# PS-VCO.net
KiCad netlist of a schematic drawn in EAGLE
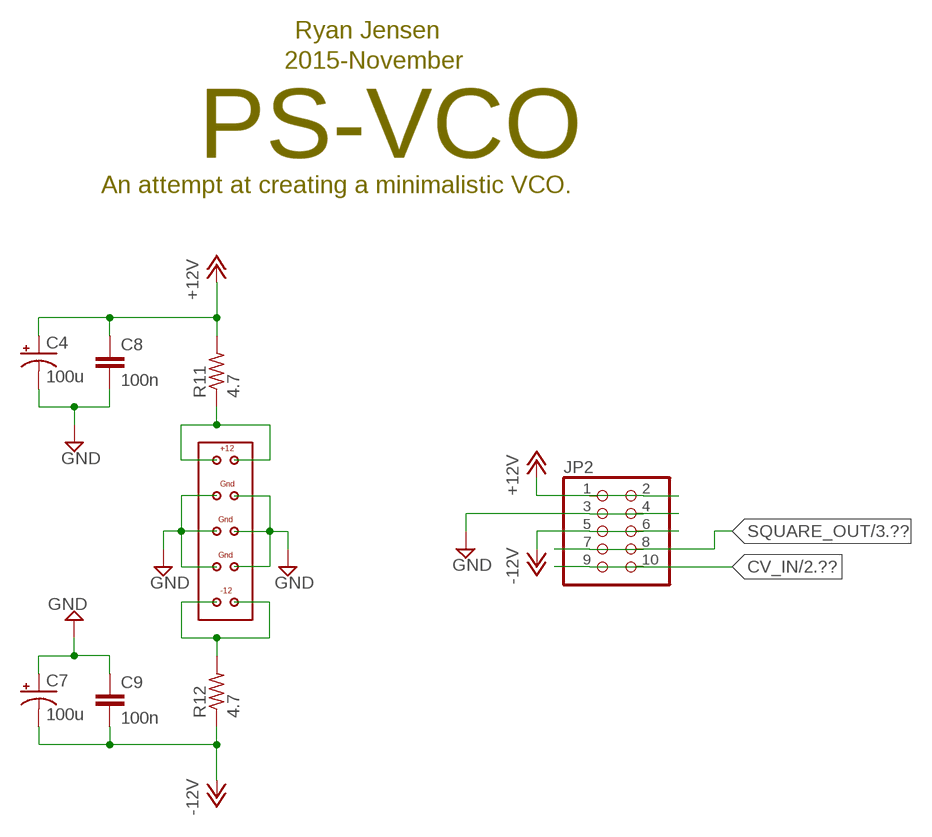
[diagram p0: schematic, sheet 1]
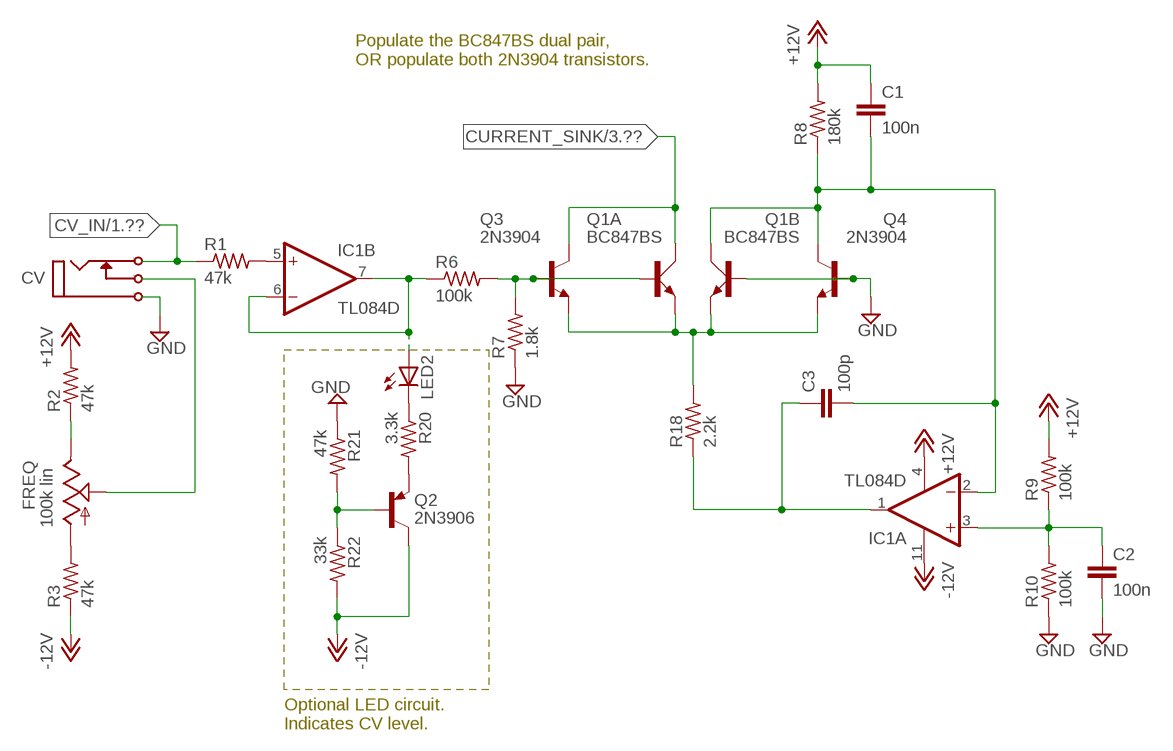
[diagram p1: schematic, sheet 2]
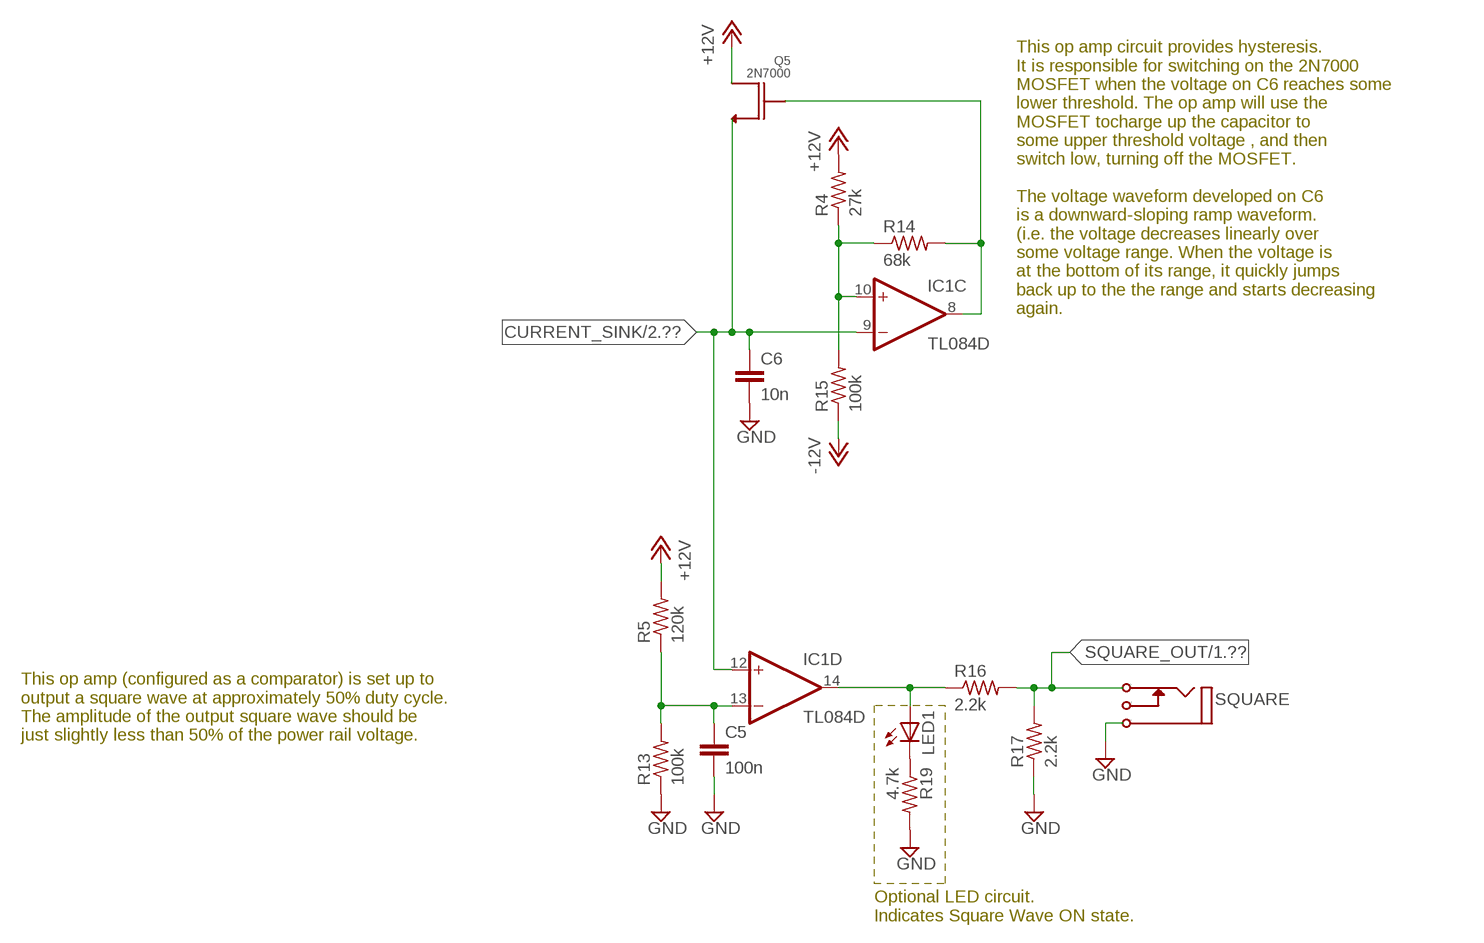
[diagram p2: schematic, sheet 3]

(export (version "E")
  (design (tool "Eeschema 10.0.6"))
  (components
    (comp (ref "C4")
      (value "100u")
      (footprint "eagle-import:E2,5-7")
      (libsource (lib "eagle-import") (part "CPOL-USE2.5-7"))
    )
    (comp (ref "C7")
      (value "100u")
      (footprint "eagle-import:E2,5-7")
      (libsource (lib "eagle-import") (part "CPOL-USE2.5-7"))
    )
    (comp (ref "C8")
      (value "100n")
      (footprint "eagle-import:C0603")
      (libsource (lib "eagle-import") (part "C-EUC0603"))
    )
    (comp (ref "C9")
      (value "100n")
      (footprint "eagle-import:C0603")
      (libsource (lib "eagle-import") (part "C-EUC0603"))
    )
    (comp (ref "JP2")
      (value "PINHD-2X5")
      (footprint "eagle-import:2X05")
      (libsource (lib "eagle-import") (part "PINHD-2X5"))
    )
    (comp (ref "R11")
      (value "4.7")
      (footprint "eagle-import:R0603")
      (libsource (lib "eagle-import") (part "R-US_R0603"))
    )
    (comp (ref "R12")
      (value "4.7")
      (footprint "eagle-import:R0603")
      (libsource (lib "eagle-import") (part "R-US_R0603"))
    )
    (comp (ref "U$3")
      (value "EURORACK-POWER")
      (footprint "eagle-import:EURORACK-POWER")
      (libsource (lib "eagle-import") (part "EURORACK-POWER"))
    )
    (comp (ref "C5")
      (value "100n")
      (footprint "eagle-import:C0603")
      (libsource (lib "eagle-import") (part "C-EUC0603"))
    )
    (comp (ref "C6")
      (value "10n")
      (footprint "eagle-import:C0603")
      (libsource (lib "eagle-import") (part "C-EUC0603"))
    )
    (comp (ref "IC1")
      (value "TL084D")
      (footprint "eagle-import:SO14")
      (libsource (lib "eagle-import") (part "TL084D"))
    )
    (comp (ref "LED1")
      (value "LED_ELD260")
      (footprint "eagle-import:LED_LD260")
      (libsource (lib "eagle-import") (part "LED_ELD260"))
    )
    (comp (ref "Q5")
      (value "2N7000")
      (footprint "eagle-import:2N7000")
      (libsource (lib "eagle-import") (part "2N7000"))
    )
    (comp (ref "R4")
      (value "27k")
      (footprint "eagle-import:R0603")
      (libsource (lib "eagle-import") (part "R-US_R0603"))
    )
    (comp (ref "R5")
      (value "120k")
      (footprint "eagle-import:R0603")
      (libsource (lib "eagle-import") (part "R-US_R0603"))
    )
    (comp (ref "R13")
      (value "100k")
      (footprint "eagle-import:R0603")
      (libsource (lib "eagle-import") (part "R-US_R0603"))
    )
    (comp (ref "R14")
      (value "68k")
      (footprint "eagle-import:R0603")
      (libsource (lib "eagle-import") (part "R-US_R0603"))
    )
    (comp (ref "R15")
      (value "100k")
      (footprint "eagle-import:R0603")
      (libsource (lib "eagle-import") (part "R-US_R0603"))
    )
    (comp (ref "R16")
      (value "2.2k")
      (footprint "eagle-import:R0603")
      (libsource (lib "eagle-import") (part "R-US_R0603"))
    )
    (comp (ref "R17")
      (value "2.2k")
      (footprint "eagle-import:R0603")
      (libsource (lib "eagle-import") (part "R-US_R0603"))
    )
    (comp (ref "R19")
      (value "4.7k")
      (footprint "eagle-import:R0603")
      (libsource (lib "eagle-import") (part "R-US_R0603"))
    )
    (comp (ref "SQUARE")
      (value "I/O")
      (footprint "eagle-import:MONO_JACK")
      (libsource (lib "eagle-import") (part "MONO_JACK"))
    )
    (comp (ref "C1")
      (value "100n")
      (footprint "eagle-import:C0603")
      (libsource (lib "eagle-import") (part "C-EUC0603"))
    )
    (comp (ref "C2")
      (value "100n")
      (footprint "eagle-import:C0603")
      (libsource (lib "eagle-import") (part "C-EUC0603"))
    )
    (comp (ref "C3")
      (value "100p")
      (footprint "eagle-import:C0603")
      (libsource (lib "eagle-import") (part "C-EUC0603"))
    )
    (comp (ref "CV")
      (value "CV")
      (footprint "eagle-import:MONO_JACK")
      (libsource (lib "eagle-import") (part "MONO_JACK"))
    )
    (comp (ref "FREQ")
      (value "100k lin")
      (footprint "eagle-import:B64Y")
      (libsource (lib "eagle-import") (part "TRIM_US-B64Y"))
    )
    (comp (ref "LED2")
      (value "LED_ELD260")
      (footprint "eagle-import:LED_LD260")
      (libsource (lib "eagle-import") (part "LED_ELD260"))
    )
    (comp (ref "Q1")
      (value "BC847BS")
      (footprint "eagle-import:SOT363_PHILIPS")
      (libsource (lib "eagle-import") (part "BC847BS"))
    )
    (comp (ref "Q2")
      (value "2N3906")
      (footprint "eagle-import:TO92")
      (libsource (lib "eagle-import") (part "2N3906"))
    )
    (comp (ref "Q3")
      (value "2N3904")
      (footprint "eagle-import:TO92")
      (libsource (lib "eagle-import") (part "2N3904"))
    )
    (comp (ref "Q4")
      (value "2N3904")
      (footprint "eagle-import:TO92")
      (libsource (lib "eagle-import") (part "2N3904"))
    )
    (comp (ref "R1")
      (value "47k")
      (footprint "eagle-import:R0603")
      (libsource (lib "eagle-import") (part "R-US_R0603"))
    )
    (comp (ref "R2")
      (value "47k")
      (footprint "eagle-import:R0603")
      (libsource (lib "eagle-import") (part "R-US_R0603"))
    )
    (comp (ref "R3")
      (value "47k")
      (footprint "eagle-import:R0603")
      (libsource (lib "eagle-import") (part "R-US_R0603"))
    )
    (comp (ref "R6")
      (value "100k")
      (footprint "eagle-import:R0603")
      (libsource (lib "eagle-import") (part "R-US_R0603"))
    )
    (comp (ref "R7")
      (value "1.8k")
      (footprint "eagle-import:R0603")
      (libsource (lib "eagle-import") (part "R-US_R0603"))
    )
    (comp (ref "R8")
      (value "180k")
      (footprint "eagle-import:R0603")
      (libsource (lib "eagle-import") (part "R-US_R0603"))
    )
    (comp (ref "R9")
      (value "100k")
      (footprint "eagle-import:R0603")
      (libsource (lib "eagle-import") (part "R-US_R0603"))
    )
    (comp (ref "R10")
      (value "100k")
      (footprint "eagle-import:R0603")
      (libsource (lib "eagle-import") (part "R-US_R0603"))
    )
    (comp (ref "R18")
      (value "2.2k")
      (footprint "eagle-import:R0603")
      (libsource (lib "eagle-import") (part "R-US_R0603"))
    )
    (comp (ref "R20")
      (value "3.3k")
      (footprint "eagle-import:R0603")
      (libsource (lib "eagle-import") (part "R-US_R0603"))
    )
    (comp (ref "R21")
      (value "47k")
      (footprint "eagle-import:R0603")
      (libsource (lib "eagle-import") (part "R-US_R0603"))
    )
    (comp (ref "R22")
      (value "33k")
      (footprint "eagle-import:R0603")
      (libsource (lib "eagle-import") (part "R-US_R0603"))
    )
  )
  (nets
    (net (code "1") (name "+12V") (class "Default")
      (node (ref "C1") (pin "1") (pinfunction "1_1") (pintype "passive"))
      (node (ref "C4") (pin "+") (pinfunction "+_+") (pintype "passive"))
      (node (ref "C8") (pin "1") (pinfunction "1_1") (pintype "passive"))
      (node (ref "IC1") (pin "4") (pinfunction "V+_4") (pintype "power_in"))
      (node (ref "JP2") (pin "1") (pinfunction "1_1") (pintype "passive"))
      (node (ref "JP2") (pin "2") (pinfunction "2_2") (pintype "passive"))
      (node (ref "Q5") (pin "D") (pinfunction "D_D") (pintype "bidirectional"))
      (node (ref "R11") (pin "2") (pinfunction "2_2") (pintype "passive"))
      (node (ref "R2") (pin "2") (pinfunction "2_2") (pintype "passive"))
      (node (ref "R4") (pin "2") (pinfunction "2_2") (pintype "passive"))
      (node (ref "R5") (pin "2") (pinfunction "2_2") (pintype "passive"))
      (node (ref "R8") (pin "2") (pinfunction "2_2") (pintype "passive"))
      (node (ref "R9") (pin "2") (pinfunction "2_2") (pintype "passive"))
    )
    (net (code "2") (name "-12V") (class "Default")
      (node (ref "C7") (pin "-") (pinfunction "-_-") (pintype "passive"))
      (node (ref "C9") (pin "2") (pinfunction "2_2") (pintype "passive"))
      (node (ref "IC1") (pin "11") (pinfunction "V-_11") (pintype "power_in"))
      (node (ref "JP2") (pin "5") (pinfunction "5_5") (pintype "passive"))
      (node (ref "JP2") (pin "6") (pinfunction "6_6") (pintype "passive"))
      (node (ref "Q2") (pin "1") (pinfunction "C_1") (pintype "passive"))
      (node (ref "R12") (pin "1") (pinfunction "1_1") (pintype "passive"))
      (node (ref "R15") (pin "1") (pinfunction "1_1") (pintype "passive"))
      (node (ref "R22") (pin "2") (pinfunction "2_2") (pintype "passive"))
      (node (ref "R3") (pin "1") (pinfunction "1_1") (pintype "passive"))
    )
    (net (code "3") (name "CURRENT_SINK") (class "Default")
      (node (ref "C6") (pin "1") (pinfunction "1_1") (pintype "passive"))
      (node (ref "IC1") (pin "12") (pinfunction "+IN_12") (pintype "input"))
      (node (ref "IC1") (pin "9") (pinfunction "-IN_9") (pintype "input"))
      (node (ref "Q1") (pin "6") (pinfunction "C_6") (pintype "passive"))
      (node (ref "Q3") (pin "1") (pinfunction "C_1") (pintype "passive"))
      (node (ref "Q5") (pin "S") (pinfunction "S_S") (pintype "bidirectional"))
    )
    (net (code "4") (name "CV_IN") (class "Default")
      (node (ref "CV") (pin "P$2") (pinfunction "P2_P$2") (pintype "bidirectional"))
      (node (ref "JP2") (pin "10") (pinfunction "10_10") (pintype "passive"))
      (node (ref "JP2") (pin "9") (pinfunction "9_9") (pintype "passive"))
      (node (ref "R1") (pin "1") (pinfunction "1_1") (pintype "passive"))
    )
    (net (code "5") (name "GND") (class "Default")
      (node (ref "C2") (pin "2") (pinfunction "2_2") (pintype "passive"))
      (node (ref "C4") (pin "-") (pinfunction "-_-") (pintype "passive"))
      (node (ref "C5") (pin "2") (pinfunction "2_2") (pintype "passive"))
      (node (ref "C6") (pin "2") (pinfunction "2_2") (pintype "passive"))
      (node (ref "C7") (pin "+") (pinfunction "+_+") (pintype "passive"))
      (node (ref "C8") (pin "2") (pinfunction "2_2") (pintype "passive"))
      (node (ref "C9") (pin "1") (pinfunction "1_1") (pintype "passive"))
      (node (ref "CV") (pin "P$1") (pinfunction "P$1_P$1") (pintype "bidirectional"))
      (node (ref "JP2") (pin "3") (pinfunction "3_3") (pintype "passive"))
      (node (ref "JP2") (pin "4") (pinfunction "4_4") (pintype "passive"))
      (node (ref "Q1") (pin "5") (pinfunction "B_5") (pintype "passive"))
      (node (ref "Q4") (pin "2") (pinfunction "B_2") (pintype "passive"))
      (node (ref "R10") (pin "1") (pinfunction "1_1") (pintype "passive"))
      (node (ref "R13") (pin "1") (pinfunction "1_1") (pintype "passive"))
      (node (ref "R17") (pin "1") (pinfunction "1_1") (pintype "passive"))
      (node (ref "R19") (pin "2") (pinfunction "2_2") (pintype "passive"))
      (node (ref "R21") (pin "1") (pinfunction "1_1") (pintype "passive"))
      (node (ref "R7") (pin "1") (pinfunction "1_1") (pintype "passive"))
      (node (ref "SQUARE") (pin "P$1") (pinfunction "P$1_P$1") (pintype "bidirectional"))
      (node (ref "U$3") (pin "P$3") (pinfunction "P$3_P$3") (pintype "bidirectional"))
      (node (ref "U$3") (pin "P$4") (pinfunction "P$4_P$4") (pintype "bidirectional"))
      (node (ref "U$3") (pin "P$5") (pinfunction "P$5_P$5") (pintype "bidirectional"))
      (node (ref "U$3") (pin "P$6") (pinfunction "P$6_P$6") (pintype "bidirectional"))
      (node (ref "U$3") (pin "P$7") (pinfunction "P$7_P$7") (pintype "bidirectional"))
      (node (ref "U$3") (pin "P$8") (pinfunction "P$8_P$8") (pintype "bidirectional"))
    )
    (net (code "6") (name "Net-(CV-P3)") (class "Default")
      (node (ref "CV") (pin "P$3") (pinfunction "P3_P$3") (pintype "bidirectional"))
      (node (ref "FREQ") (pin "S") (pinfunction "S_S") (pintype "passive"))
    )
    (net (code "7") (name "Net-(FREQ-PadA)") (class "Default")
      (node (ref "FREQ") (pin "A") (pinfunction "A_A") (pintype "passive"))
      (node (ref "R3") (pin "2") (pinfunction "2_2") (pintype "passive"))
    )
    (net (code "8") (name "Net-(FREQ-PadE)") (class "Default")
      (node (ref "FREQ") (pin "E") (pinfunction "E_E") (pintype "passive"))
      (node (ref "R2") (pin "1") (pinfunction "1_1") (pintype "passive"))
    )
    (net (code "9") (name "Net-(IC1A-+IN)") (class "Default")
      (node (ref "C2") (pin "1") (pinfunction "1_1") (pintype "passive"))
      (node (ref "IC1") (pin "3") (pinfunction "+IN_3") (pintype "input"))
      (node (ref "R10") (pin "2") (pinfunction "2_2") (pintype "passive"))
      (node (ref "R9") (pin "1") (pinfunction "1_1") (pintype "passive"))
    )
    (net (code "10") (name "Net-(IC1A--IN)") (class "Default")
      (node (ref "C1") (pin "2") (pinfunction "2_2") (pintype "passive"))
      (node (ref "C3") (pin "2") (pinfunction "2_2") (pintype "passive"))
      (node (ref "IC1") (pin "2") (pinfunction "-IN_2") (pintype "input"))
      (node (ref "Q1") (pin "3") (pinfunction "C_3") (pintype "passive"))
      (node (ref "Q4") (pin "1") (pinfunction "C_1") (pintype "passive"))
      (node (ref "R8") (pin "1") (pinfunction "1_1") (pintype "passive"))
    )
    (net (code "11") (name "Net-(IC1A-OUT)") (class "Default")
      (node (ref "C3") (pin "1") (pinfunction "1_1") (pintype "passive"))
      (node (ref "IC1") (pin "1") (pinfunction "OUT_1") (pintype "output"))
      (node (ref "R18") (pin "1") (pinfunction "1_1") (pintype "passive"))
    )
    (net (code "12") (name "Net-(IC1B-+IN)") (class "Default")
      (node (ref "IC1") (pin "5") (pinfunction "+IN_5") (pintype "input"))
      (node (ref "R1") (pin "2") (pinfunction "2_2") (pintype "passive"))
    )
    (net (code "13") (name "Net-(IC1B--IN)") (class "Default")
      (node (ref "IC1") (pin "6") (pinfunction "-IN_6") (pintype "input"))
      (node (ref "IC1") (pin "7") (pinfunction "OUT_7") (pintype "output"))
      (node (ref "LED2") (pin "A") (pinfunction "A_A") (pintype "passive"))
      (node (ref "R6") (pin "1") (pinfunction "1_1") (pintype "passive"))
    )
    (net (code "14") (name "Net-(IC1C-+IN)") (class "Default")
      (node (ref "IC1") (pin "10") (pinfunction "+IN_10") (pintype "input"))
      (node (ref "R14") (pin "1") (pinfunction "1_1") (pintype "passive"))
      (node (ref "R15") (pin "2") (pinfunction "2_2") (pintype "passive"))
      (node (ref "R4") (pin "1") (pinfunction "1_1") (pintype "passive"))
    )
    (net (code "15") (name "Net-(IC1C-OUT)") (class "Default")
      (node (ref "IC1") (pin "8") (pinfunction "OUT_8") (pintype "output"))
      (node (ref "Q5") (pin "G") (pinfunction "G_G") (pintype "bidirectional"))
      (node (ref "R14") (pin "2") (pinfunction "2_2") (pintype "passive"))
    )
    (net (code "16") (name "Net-(IC1D--IN)") (class "Default")
      (node (ref "C5") (pin "1") (pinfunction "1_1") (pintype "passive"))
      (node (ref "IC1") (pin "13") (pinfunction "-IN_13") (pintype "input"))
      (node (ref "R13") (pin "2") (pinfunction "2_2") (pintype "passive"))
      (node (ref "R5") (pin "1") (pinfunction "1_1") (pintype "passive"))
    )
    (net (code "17") (name "Net-(IC1D-OUT)") (class "Default")
      (node (ref "IC1") (pin "14") (pinfunction "OUT_14") (pintype "output"))
      (node (ref "LED1") (pin "A") (pinfunction "A_A") (pintype "passive"))
      (node (ref "R16") (pin "1") (pinfunction "1_1") (pintype "passive"))
    )
    (net (code "18") (name "Net-(LED1-C)") (class "Default")
      (node (ref "LED1") (pin "K") (pinfunction "C_K") (pintype "passive"))
      (node (ref "R19") (pin "1") (pinfunction "1_1") (pintype "passive"))
    )
    (net (code "19") (name "Net-(LED2-C)") (class "Default")
      (node (ref "LED2") (pin "K") (pinfunction "C_K") (pintype "passive"))
      (node (ref "R20") (pin "1") (pinfunction "1_1") (pintype "passive"))
    )
    (net (code "20") (name "Net-(Q1A-B)") (class "Default")
      (node (ref "Q1") (pin "2") (pinfunction "B_2") (pintype "passive"))
      (node (ref "Q3") (pin "2") (pinfunction "B_2") (pintype "passive"))
      (node (ref "R6") (pin "2") (pinfunction "2_2") (pintype "passive"))
      (node (ref "R7") (pin "2") (pinfunction "2_2") (pintype "passive"))
    )
    (net (code "21") (name "Net-(Q1A-E)") (class "Default")
      (node (ref "Q1") (pin "1") (pinfunction "E_1") (pintype "passive"))
      (node (ref "Q1") (pin "4") (pinfunction "E_4") (pintype "passive"))
      (node (ref "Q3") (pin "3") (pinfunction "E_3") (pintype "passive"))
      (node (ref "Q4") (pin "3") (pinfunction "E_3") (pintype "passive"))
      (node (ref "R18") (pin "2") (pinfunction "2_2") (pintype "passive"))
    )
    (net (code "22") (name "Net-(Q2-B)") (class "Default")
      (node (ref "Q2") (pin "2") (pinfunction "B_2") (pintype "passive"))
      (node (ref "R21") (pin "2") (pinfunction "2_2") (pintype "passive"))
      (node (ref "R22") (pin "1") (pinfunction "1_1") (pintype "passive"))
    )
    (net (code "23") (name "Net-(Q2-E)") (class "Default")
      (node (ref "Q2") (pin "3") (pinfunction "E_3") (pintype "passive"))
      (node (ref "R20") (pin "2") (pinfunction "2_2") (pintype "passive"))
    )
    (net (code "24") (name "Net-(R11-Pad1)") (class "Default")
      (node (ref "R11") (pin "1") (pinfunction "1_1") (pintype "passive"))
      (node (ref "U$3") (pin "P$1") (pinfunction "P$1_P$1") (pintype "bidirectional"))
      (node (ref "U$3") (pin "P$2") (pinfunction "P$2_P$2") (pintype "bidirectional"))
    )
    (net (code "25") (name "Net-(R12-Pad2)") (class "Default")
      (node (ref "R12") (pin "2") (pinfunction "2_2") (pintype "passive"))
      (node (ref "U$3") (pin "P$10") (pinfunction "P$10_P$10") (pintype "bidirectional"))
      (node (ref "U$3") (pin "P$9") (pinfunction "P$9_P$9") (pintype "bidirectional"))
    )
    (net (code "26") (name "SQUARE_OUT") (class "Default")
      (node (ref "JP2") (pin "7") (pinfunction "7_7") (pintype "passive"))
      (node (ref "JP2") (pin "8") (pinfunction "8_8") (pintype "passive"))
      (node (ref "R16") (pin "2") (pinfunction "2_2") (pintype "passive"))
      (node (ref "R17") (pin "2") (pinfunction "2_2") (pintype "passive"))
      (node (ref "SQUARE") (pin "P$2") (pinfunction "P2_P$2") (pintype "bidirectional"))
    )
    (net (code "27") (name "unconnected-(SQUARE-P3-PadP$3)") (class "Default")
      (node (ref "SQUARE") (pin "P$3") (pinfunction "P3_P$3") (pintype "bidirectional"))
    )
  )
)
